# 2-APA102-IO.net
KiCad netlist of a schematic drawn in EAGLE
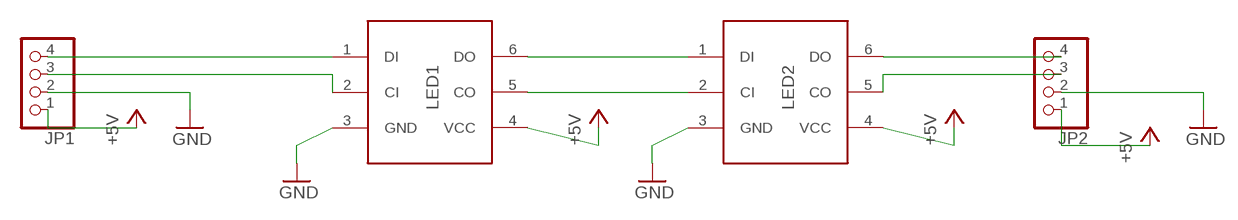
[diagram p0: schematic, sheet 1]

(export (version "E")
  (design (tool "Eeschema 10.0.6"))
  (components
    (comp (ref "JP1")
      (value "PINHD-1X4")
      (footprint "eagle-import:1X04")
      (libsource (lib "eagle-import") (part "PINHD-1X4"))
    )
    (comp (ref "JP2")
      (value "PINHD-1X4")
      (footprint "eagle-import:1X04")
      (libsource (lib "eagle-import") (part "PINHD-1X4"))
    )
    (comp (ref "LED1")
      (value "APA1025050")
      (footprint "eagle-import:APA1025050")
      (libsource (lib "eagle-import") (part "APA1025050"))
    )
    (comp (ref "LED2")
      (value "APA1025050")
      (footprint "eagle-import:APA1025050")
      (libsource (lib "eagle-import") (part "APA1025050"))
    )
  )
  (nets
    (net (code "1") (name "+5V") (class "Default")
      (node (ref "JP1") (pin "1") (pinfunction "1_1") (pintype "passive"))
      (node (ref "JP2") (pin "1") (pinfunction "1_1") (pintype "passive"))
      (node (ref "LED1") (pin "4") (pinfunction "VCC_4") (pintype "power_in"))
      (node (ref "LED2") (pin "4") (pinfunction "VCC_4") (pintype "power_in"))
    )
    (net (code "2") (name "GND") (class "Default")
      (node (ref "JP1") (pin "2") (pinfunction "2_2") (pintype "passive"))
      (node (ref "JP2") (pin "2") (pinfunction "2_2") (pintype "passive"))
      (node (ref "LED1") (pin "3") (pinfunction "GND_3") (pintype "power_in"))
      (node (ref "LED2") (pin "3") (pinfunction "GND_3") (pintype "power_in"))
    )
    (net (code "3") (name "Net-(LED1-CI)") (class "Default")
      (node (ref "JP1") (pin "3") (pinfunction "3_3") (pintype "passive"))
      (node (ref "LED1") (pin "2") (pinfunction "CI_2") (pintype "input"))
    )
    (net (code "4") (name "Net-(LED1-CO)") (class "Default")
      (node (ref "LED1") (pin "5") (pinfunction "CO_5") (pintype "output"))
      (node (ref "LED2") (pin "2") (pinfunction "CI_2") (pintype "input"))
    )
    (net (code "5") (name "Net-(LED1-DI)") (class "Default")
      (node (ref "JP1") (pin "4") (pinfunction "4_4") (pintype "passive"))
      (node (ref "LED1") (pin "1") (pinfunction "DI_1") (pintype "input"))
    )
    (net (code "6") (name "Net-(LED1-DO)") (class "Default")
      (node (ref "LED1") (pin "6") (pinfunction "DO_6") (pintype "output"))
      (node (ref "LED2") (pin "1") (pinfunction "DI_1") (pintype "input"))
    )
    (net (code "7") (name "Net-(LED2-CO)") (class "Default")
      (node (ref "JP2") (pin "3") (pinfunction "3_3") (pintype "passive"))
      (node (ref "LED2") (pin "5") (pinfunction "CO_5") (pintype "output"))
    )
    (net (code "8") (name "Net-(LED2-DO)") (class "Default")
      (node (ref "JP2") (pin "4") (pinfunction "4_4") (pintype "passive"))
      (node (ref "LED2") (pin "6") (pinfunction "DO_6") (pintype "output"))
    )
  )
)
